# Sheet.net
KiCad netlist of a schematic drawn in Altium Designer
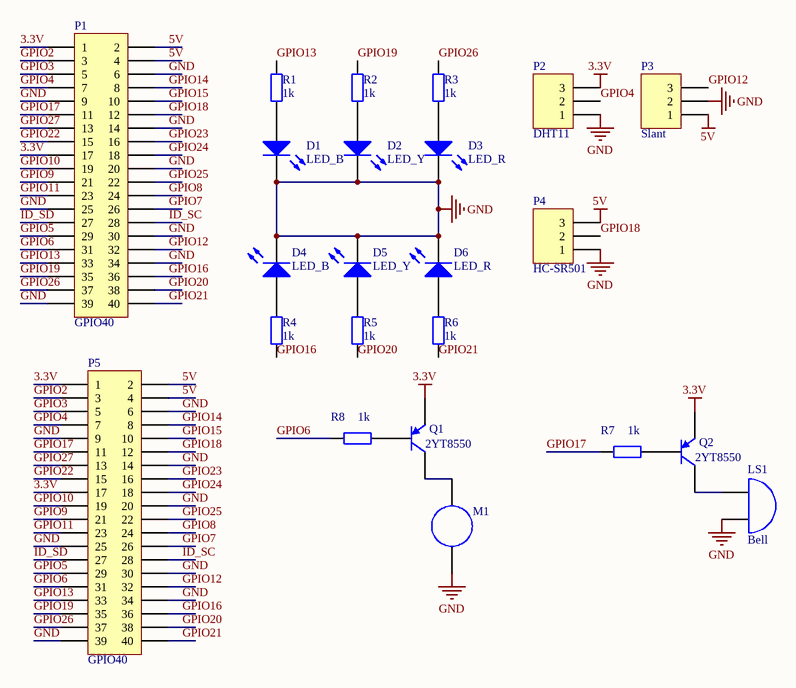
[diagram p0: Sheet.SchDoc]

(export (version "E")
  (design (tool "Eeschema 10.0.6"))
  (components
    (comp (ref "D1")
      (value "LED_B")
      (footprint "R38")
      (description "Typical INFRARED GaAs LED")
      (fields (field (name "PUBLISHER") "Altium Limited"))
      (libsource (lib "Miscellaneous Devices") (part "LED0"))
    )
    (comp (ref "D2")
      (value "LED_Y")
      (footprint "R38")
      (description "Typical INFRARED GaAs LED")
      (fields (field (name "PUBLISHER") "Altium Limited"))
      (libsource (lib "Miscellaneous Devices") (part "LED0"))
    )
    (comp (ref "D3")
      (value "LED_R")
      (footprint "R38")
      (description "Typical INFRARED GaAs LED")
      (fields (field (name "PUBLISHER") "Altium Limited"))
      (libsource (lib "Miscellaneous Devices") (part "LED0"))
    )
    (comp (ref "D4")
      (value "LED_B")
      (footprint "R38")
      (description "Typical INFRARED GaAs LED")
      (fields (field (name "PUBLISHER") "Altium Limited"))
      (libsource (lib "Miscellaneous Devices") (part "LED0"))
    )
    (comp (ref "D5")
      (value "LED_Y")
      (footprint "R38")
      (description "Typical INFRARED GaAs LED")
      (fields (field (name "PUBLISHER") "Altium Limited"))
      (libsource (lib "Miscellaneous Devices") (part "LED0"))
    )
    (comp (ref "D6")
      (value "LED_R")
      (footprint "R38")
      (description "Typical INFRARED GaAs LED")
      (fields (field (name "PUBLISHER") "Altium Limited"))
      (libsource (lib "Miscellaneous Devices") (part "LED0"))
    )
    (comp (ref "LS1")
      (value "Bell")
      (footprint "BUZZ12")
      (description "Electrical Bell")
      (fields (field (name "PUBLISHER") "Altium Limited"))
      (libsource (lib "Miscellaneous Devices") (part "Bell"))
    )
    (comp (ref "M1")
      (value "Meter")
      (footprint "RAD-0.1")
      (description "Indicating Instrument")
      (fields (field (name "PUBLISHER") "Altium Limited"))
      (libsource (lib "Miscellaneous Devices") (part "Meter"))
    )
    (comp (ref "P1")
      (value "GPIO40")
      (footprint "HDR2X20")
      (description "Header, 20-Pin, Dual row")
      (fields (field (name "PUBLISHER") "Altium Limited"))
      (libsource (lib "Miscellaneous Connectors") (part "Header 20X2"))
    )
    (comp (ref "P2")
      (value "DHT11")
      (footprint "HDR1X3")
      (description "Header, 3-Pin")
      (fields (field (name "PUBLISHER") "Altium Limited"))
      (libsource (lib "Miscellaneous Connectors") (part "Header 3"))
    )
    (comp (ref "P3")
      (value "Slant")
      (footprint "HDR1X3")
      (description "Header, 3-Pin")
      (fields (field (name "PUBLISHER") "Altium Limited"))
      (libsource (lib "Miscellaneous Connectors") (part "Header 3"))
    )
    (comp (ref "P4")
      (value "HC-SR501")
      (footprint "HDR1X3")
      (description "Header, 3-Pin")
      (fields (field (name "PUBLISHER") "Altium Limited"))
      (libsource (lib "Miscellaneous Connectors") (part "Header 3"))
    )
    (comp (ref "P5")
      (value "GPIO40")
      (footprint "HDR2X20")
      (description "Header, 20-Pin, Dual row")
      (fields (field (name "PUBLISHER") "Altium Limited"))
      (libsource (lib "Miscellaneous Connectors") (part "Header 20X2"))
    )
    (comp (ref "Q1") (value "2YT8550") (footprint "SOT-23-3") (libsource (lib "Schematic") (part "2YT8550")))
    (comp (ref "Q2") (value "2YT8550") (footprint "SOT-23-3") (libsource (lib "Schematic") (part "2YT8550")))
    (comp (ref "R1")
      (value "1k")
      (footprint "R0805")
      (description "Resistor 0603 1%")
      (fields (field (name "PUBLISHER") "Altium Limited"))
      (libsource (lib "") (part "Res2_1"))
    )
    (comp (ref "R2")
      (value "1k")
      (footprint "R0805")
      (description "Resistor 0603 1%")
      (fields (field (name "PUBLISHER") "Altium Limited"))
      (libsource (lib "") (part "Res2_1"))
    )
    (comp (ref "R3")
      (value "1k")
      (footprint "R0805")
      (description "Resistor 0603 1%")
      (fields (field (name "PUBLISHER") "Altium Limited"))
      (libsource (lib "") (part "Res2_1"))
    )
    (comp (ref "R4")
      (value "1k")
      (footprint "R0805")
      (description "Resistor 0603 1%")
      (fields (field (name "PUBLISHER") "Altium Limited"))
      (libsource (lib "") (part "Res2_1"))
    )
    (comp (ref "R5")
      (value "1k")
      (footprint "R0805")
      (description "Resistor 0603 1%")
      (fields (field (name "PUBLISHER") "Altium Limited"))
      (libsource (lib "") (part "Res2_1"))
    )
    (comp (ref "R6")
      (value "1k")
      (footprint "R0805")
      (description "Resistor 0603 1%")
      (fields (field (name "PUBLISHER") "Altium Limited"))
      (libsource (lib "") (part "Res2_1"))
    )
    (comp (ref "R7")
      (value "1k")
      (footprint "R0805")
      (description "Resistor 0603 1%")
      (fields (field (name "PUBLISHER") "Altium Limited"))
      (libsource (lib "makeblockScratchRobot") (part "Res2"))
    )
    (comp (ref "R8")
      (value "1k")
      (footprint "R0805")
      (description "Resistor 0603 1%")
      (fields (field (name "PUBLISHER") "Altium Limited"))
      (libsource (lib "makeblockScratchRobot") (part "Res2"))
    )
  )
  (nets
    (net (code "1") (name "/GPIO2") (class "Default")
      (node (ref "P1") (pin "3") (pinfunction "3_3") (pintype "passive"))
      (node (ref "P5") (pin "3") (pinfunction "3_3") (pintype "passive"))
    )
    (net (code "2") (name "/GPIO3") (class "Default")
      (node (ref "P1") (pin "5") (pinfunction "5_5") (pintype "passive"))
      (node (ref "P5") (pin "5") (pinfunction "5_5") (pintype "passive"))
    )
    (net (code "3") (name "/GPIO4") (class "Default")
      (node (ref "P1") (pin "7") (pinfunction "7_7") (pintype "passive"))
      (node (ref "P2") (pin "2") (pinfunction "2_2") (pintype "passive"))
      (node (ref "P5") (pin "7") (pinfunction "7_7") (pintype "passive"))
    )
    (net (code "4") (name "/GPIO5") (class "Default")
      (node (ref "P1") (pin "29") (pinfunction "29_29") (pintype "passive"))
      (node (ref "P5") (pin "29") (pinfunction "29_29") (pintype "passive"))
    )
    (net (code "5") (name "/GPIO6") (class "Default")
      (node (ref "P1") (pin "31") (pinfunction "31_31") (pintype "passive"))
      (node (ref "P5") (pin "31") (pinfunction "31_31") (pintype "passive"))
      (node (ref "R8") (pin "1") (pinfunction "1_1") (pintype "passive"))
    )
    (net (code "6") (name "/GPIO7") (class "Default")
      (node (ref "P1") (pin "26") (pinfunction "26_26") (pintype "passive"))
      (node (ref "P5") (pin "26") (pinfunction "26_26") (pintype "passive"))
    )
    (net (code "7") (name "/GPIO8") (class "Default")
      (node (ref "P1") (pin "24") (pinfunction "24_24") (pintype "passive"))
      (node (ref "P5") (pin "24") (pinfunction "24_24") (pintype "passive"))
    )
    (net (code "8") (name "/GPIO9") (class "Default")
      (node (ref "P1") (pin "21") (pinfunction "21_21") (pintype "passive"))
      (node (ref "P5") (pin "21") (pinfunction "21_21") (pintype "passive"))
    )
    (net (code "9") (name "/GPIO10") (class "Default")
      (node (ref "P1") (pin "19") (pinfunction "19_19") (pintype "passive"))
      (node (ref "P5") (pin "19") (pinfunction "19_19") (pintype "passive"))
    )
    (net (code "10") (name "/GPIO11") (class "Default")
      (node (ref "P1") (pin "23") (pinfunction "23_23") (pintype "passive"))
      (node (ref "P5") (pin "23") (pinfunction "23_23") (pintype "passive"))
    )
    (net (code "11") (name "/GPIO12") (class "Default")
      (node (ref "P1") (pin "32") (pinfunction "32_32") (pintype "passive"))
      (node (ref "P3") (pin "3") (pinfunction "3_3") (pintype "passive"))
      (node (ref "P5") (pin "32") (pinfunction "32_32") (pintype "passive"))
    )
    (net (code "12") (name "/GPIO13") (class "Default")
      (node (ref "P1") (pin "33") (pinfunction "33_33") (pintype "passive"))
      (node (ref "P5") (pin "33") (pinfunction "33_33") (pintype "passive"))
      (node (ref "R1") (pin "2") (pinfunction "2_2") (pintype "passive"))
    )
    (net (code "13") (name "/GPIO14") (class "Default")
      (node (ref "P1") (pin "8") (pinfunction "8_8") (pintype "passive"))
      (node (ref "P5") (pin "8") (pinfunction "8_8") (pintype "passive"))
    )
    (net (code "14") (name "/GPIO15") (class "Default")
      (node (ref "P1") (pin "10") (pinfunction "10_10") (pintype "passive"))
      (node (ref "P5") (pin "10") (pinfunction "10_10") (pintype "passive"))
    )
    (net (code "15") (name "/GPIO16") (class "Default")
      (node (ref "P1") (pin "36") (pinfunction "36_36") (pintype "passive"))
      (node (ref "P5") (pin "36") (pinfunction "36_36") (pintype "passive"))
      (node (ref "R4") (pin "1") (pinfunction "1_1") (pintype "passive"))
    )
    (net (code "16") (name "/GPIO17") (class "Default")
      (node (ref "P1") (pin "11") (pinfunction "11_11") (pintype "passive"))
      (node (ref "P5") (pin "11") (pinfunction "11_11") (pintype "passive"))
      (node (ref "R7") (pin "1") (pinfunction "1_1") (pintype "passive"))
    )
    (net (code "17") (name "/GPIO18") (class "Default")
      (node (ref "P1") (pin "12") (pinfunction "12_12") (pintype "passive"))
      (node (ref "P4") (pin "2") (pinfunction "2_2") (pintype "passive"))
      (node (ref "P5") (pin "12") (pinfunction "12_12") (pintype "passive"))
    )
    (net (code "18") (name "/GPIO19") (class "Default")
      (node (ref "P1") (pin "35") (pinfunction "35_35") (pintype "passive"))
      (node (ref "P5") (pin "35") (pinfunction "35_35") (pintype "passive"))
      (node (ref "R2") (pin "2") (pinfunction "2_2") (pintype "passive"))
    )
    (net (code "19") (name "/GPIO20") (class "Default")
      (node (ref "P1") (pin "38") (pinfunction "38_38") (pintype "passive"))
      (node (ref "P5") (pin "38") (pinfunction "38_38") (pintype "passive"))
      (node (ref "R5") (pin "1") (pinfunction "1_1") (pintype "passive"))
    )
    (net (code "20") (name "/GPIO21") (class "Default")
      (node (ref "P1") (pin "40") (pinfunction "40_40") (pintype "passive"))
      (node (ref "P5") (pin "40") (pinfunction "40_40") (pintype "passive"))
      (node (ref "R6") (pin "1") (pinfunction "1_1") (pintype "passive"))
    )
    (net (code "21") (name "/GPIO22") (class "Default")
      (node (ref "P1") (pin "15") (pinfunction "15_15") (pintype "passive"))
      (node (ref "P5") (pin "15") (pinfunction "15_15") (pintype "passive"))
    )
    (net (code "22") (name "/GPIO23") (class "Default")
      (node (ref "P1") (pin "16") (pinfunction "16_16") (pintype "passive"))
      (node (ref "P5") (pin "16") (pinfunction "16_16") (pintype "passive"))
    )
    (net (code "23") (name "/GPIO24") (class "Default")
      (node (ref "P1") (pin "18") (pinfunction "18_18") (pintype "passive"))
      (node (ref "P5") (pin "18") (pinfunction "18_18") (pintype "passive"))
    )
    (net (code "24") (name "/GPIO25") (class "Default")
      (node (ref "P1") (pin "22") (pinfunction "22_22") (pintype "passive"))
      (node (ref "P5") (pin "22") (pinfunction "22_22") (pintype "passive"))
    )
    (net (code "25") (name "/GPIO26") (class "Default")
      (node (ref "P1") (pin "37") (pinfunction "37_37") (pintype "passive"))
      (node (ref "P5") (pin "37") (pinfunction "37_37") (pintype "passive"))
      (node (ref "R3") (pin "2") (pinfunction "2_2") (pintype "passive"))
    )
    (net (code "26") (name "/GPIO27") (class "Default")
      (node (ref "P1") (pin "13") (pinfunction "13_13") (pintype "passive"))
      (node (ref "P5") (pin "13") (pinfunction "13_13") (pintype "passive"))
    )
    (net (code "27") (name "/ID_SC") (class "Default")
      (node (ref "P1") (pin "28") (pinfunction "28_28") (pintype "passive"))
      (node (ref "P5") (pin "28") (pinfunction "28_28") (pintype "passive"))
    )
    (net (code "28") (name "/ID_SD") (class "Default")
      (node (ref "P1") (pin "27") (pinfunction "27_27") (pintype "passive"))
      (node (ref "P5") (pin "27") (pinfunction "27_27") (pintype "passive"))
    )
    (net (code "29") (name "3.3V") (class "Default")
      (node (ref "P1") (pin "1") (pinfunction "1_1") (pintype "passive"))
      (node (ref "P1") (pin "17") (pinfunction "17_17") (pintype "passive"))
      (node (ref "P2") (pin "3") (pinfunction "3_3") (pintype "passive"))
      (node (ref "P5") (pin "1") (pinfunction "1_1") (pintype "passive"))
      (node (ref "P5") (pin "17") (pinfunction "17_17") (pintype "passive"))
      (node (ref "Q1") (pin "2") (pinfunction "E_2") (pintype "passive"))
      (node (ref "Q2") (pin "2") (pinfunction "E_2") (pintype "passive"))
    )
    (net (code "30") (name "5V") (class "Default")
      (node (ref "P1") (pin "2") (pinfunction "2_2") (pintype "passive"))
      (node (ref "P1") (pin "4") (pinfunction "4_4") (pintype "passive"))
      (node (ref "P3") (pin "1") (pinfunction "1_1") (pintype "passive"))
      (node (ref "P4") (pin "3") (pinfunction "3_3") (pintype "passive"))
      (node (ref "P5") (pin "2") (pinfunction "2_2") (pintype "passive"))
      (node (ref "P5") (pin "4") (pinfunction "4_4") (pintype "passive"))
    )
    (net (code "31") (name "GND") (class "Default")
      (node (ref "D1") (pin "2") (pinfunction "K_2") (pintype "passive"))
      (node (ref "D2") (pin "2") (pinfunction "K_2") (pintype "passive"))
      (node (ref "D3") (pin "2") (pinfunction "K_2") (pintype "passive"))
      (node (ref "D4") (pin "2") (pinfunction "K_2") (pintype "passive"))
      (node (ref "D5") (pin "2") (pinfunction "K_2") (pintype "passive"))
      (node (ref "D6") (pin "2") (pinfunction "K_2") (pintype "passive"))
      (node (ref "LS1") (pin "2") (pinfunction "B_2") (pintype "passive"))
      (node (ref "M1") (pin "1") (pinfunction "1_1") (pintype "passive"))
      (node (ref "P1") (pin "14") (pinfunction "14_14") (pintype "passive"))
      (node (ref "P1") (pin "20") (pinfunction "20_20") (pintype "passive"))
      (node (ref "P1") (pin "25") (pinfunction "25_25") (pintype "passive"))
      (node (ref "P1") (pin "30") (pinfunction "30_30") (pintype "passive"))
      (node (ref "P1") (pin "34") (pinfunction "34_34") (pintype "passive"))
      (node (ref "P1") (pin "39") (pinfunction "39_39") (pintype "passive"))
      (node (ref "P1") (pin "6") (pinfunction "6_6") (pintype "passive"))
      (node (ref "P1") (pin "9") (pinfunction "9_9") (pintype "passive"))
      (node (ref "P2") (pin "1") (pinfunction "1_1") (pintype "passive"))
      (node (ref "P3") (pin "2") (pinfunction "2_2") (pintype "passive"))
      (node (ref "P4") (pin "1") (pinfunction "1_1") (pintype "passive"))
      (node (ref "P5") (pin "14") (pinfunction "14_14") (pintype "passive"))
      (node (ref "P5") (pin "20") (pinfunction "20_20") (pintype "passive"))
      (node (ref "P5") (pin "25") (pinfunction "25_25") (pintype "passive"))
      (node (ref "P5") (pin "30") (pinfunction "30_30") (pintype "passive"))
      (node (ref "P5") (pin "34") (pinfunction "34_34") (pintype "passive"))
      (node (ref "P5") (pin "39") (pinfunction "39_39") (pintype "passive"))
      (node (ref "P5") (pin "6") (pinfunction "6_6") (pintype "passive"))
      (node (ref "P5") (pin "9") (pinfunction "9_9") (pintype "passive"))
    )
    (net (code "32") (name "Net-(D1-A)") (class "Default")
      (node (ref "D1") (pin "1") (pinfunction "A_1") (pintype "passive"))
      (node (ref "R1") (pin "1") (pinfunction "1_1") (pintype "passive"))
    )
    (net (code "33") (name "Net-(D2-A)") (class "Default")
      (node (ref "D2") (pin "1") (pinfunction "A_1") (pintype "passive"))
      (node (ref "R2") (pin "1") (pinfunction "1_1") (pintype "passive"))
    )
    (net (code "34") (name "Net-(D3-A)") (class "Default")
      (node (ref "D3") (pin "1") (pinfunction "A_1") (pintype "passive"))
      (node (ref "R3") (pin "1") (pinfunction "1_1") (pintype "passive"))
    )
    (net (code "35") (name "Net-(D4-A)") (class "Default")
      (node (ref "D4") (pin "1") (pinfunction "A_1") (pintype "passive"))
      (node (ref "R4") (pin "2") (pinfunction "2_2") (pintype "passive"))
    )
    (net (code "36") (name "Net-(D5-A)") (class "Default")
      (node (ref "D5") (pin "1") (pinfunction "A_1") (pintype "passive"))
      (node (ref "R5") (pin "2") (pinfunction "2_2") (pintype "passive"))
    )
    (net (code "37") (name "Net-(D6-A)") (class "Default")
      (node (ref "D6") (pin "1") (pinfunction "A_1") (pintype "passive"))
      (node (ref "R6") (pin "2") (pinfunction "2_2") (pintype "passive"))
    )
    (net (code "38") (name "Net-(LS1-A)") (class "Default")
      (node (ref "LS1") (pin "1") (pinfunction "A_1") (pintype "passive"))
      (node (ref "Q2") (pin "3") (pinfunction "C_3") (pintype "passive"))
    )
    (net (code "39") (name "Net-(Q1-B)") (class "Default")
      (node (ref "Q1") (pin "1") (pinfunction "B_1") (pintype "passive"))
      (node (ref "R8") (pin "2") (pinfunction "2_2") (pintype "passive"))
    )
    (net (code "40") (name "Net-(Q1-C)") (class "Default")
      (node (ref "M1") (pin "2") (pinfunction "2_2") (pintype "passive"))
      (node (ref "Q1") (pin "3") (pinfunction "C_3") (pintype "passive"))
    )
    (net (code "41") (name "Net-(Q2-B)") (class "Default")
      (node (ref "Q2") (pin "1") (pinfunction "B_1") (pintype "passive"))
      (node (ref "R7") (pin "2") (pinfunction "2_2") (pintype "passive"))
    )
  )
)
